# UniversalGlucometerV3.net
KiCad netlist of a schematic drawn in EAGLE
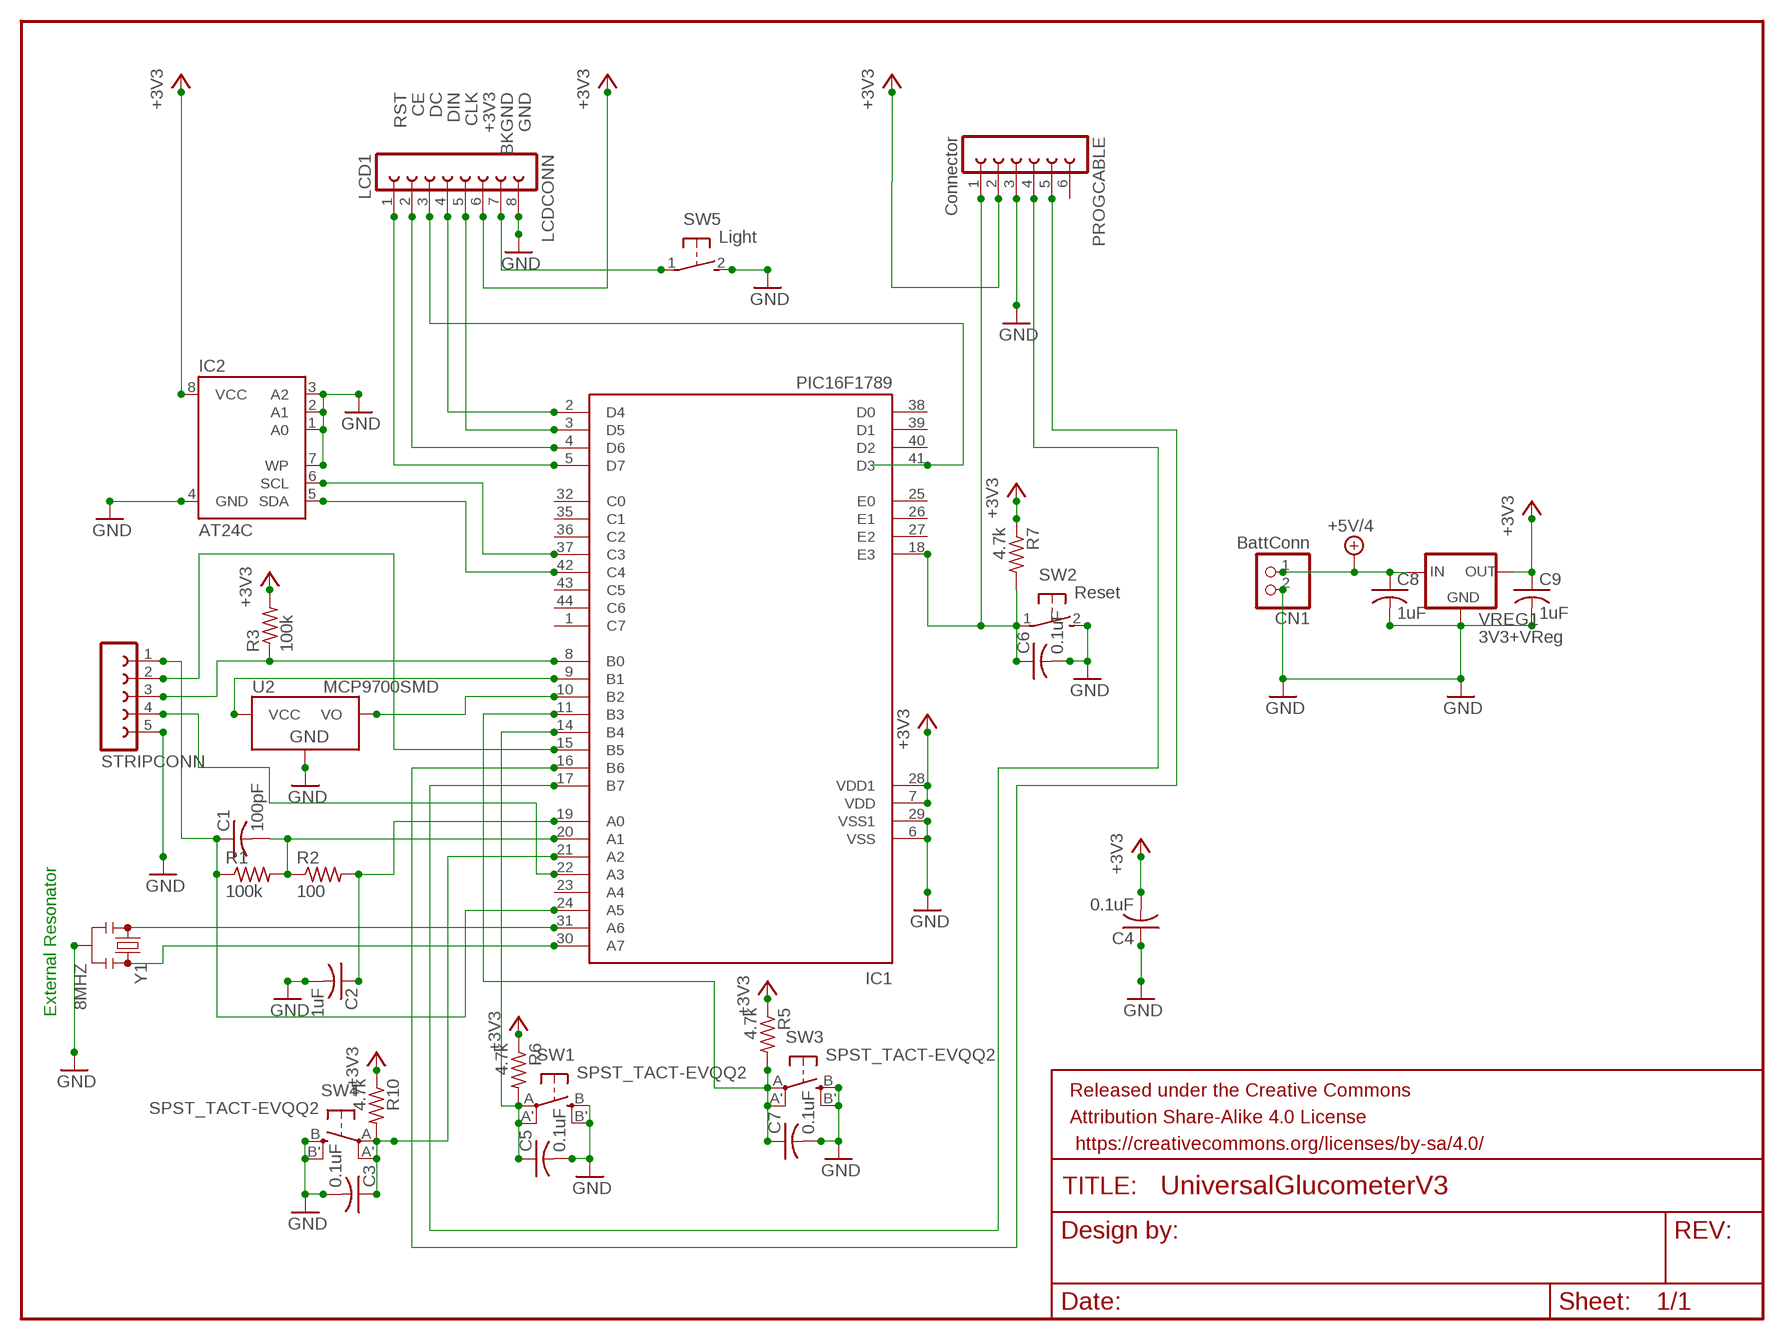
[diagram p0: schematic, sheet 1]

(export (version "E")
  (design (tool "Eeschema 10.0.6"))
  (components
    (comp (ref "C1")
      (value "100pF")
      (footprint "eagle-import:C0805")
      (libsource (lib "eagle-import") (part "C-USC0805"))
    )
    (comp (ref "C2")
      (value "1uF")
      (footprint "eagle-import:C0805")
      (libsource (lib "eagle-import") (part "C-USC0805"))
    )
    (comp (ref "C3")
      (value "0.1uF")
      (footprint "eagle-import:C0805")
      (libsource (lib "eagle-import") (part "C-USC0805"))
    )
    (comp (ref "C4")
      (value "0.1uF")
      (footprint "eagle-import:C0805")
      (libsource (lib "eagle-import") (part "C-USC0805"))
    )
    (comp (ref "C5")
      (value "0.1uF")
      (footprint "eagle-import:C0805")
      (libsource (lib "eagle-import") (part "C-USC0805"))
    )
    (comp (ref "C6")
      (value "0.1uF")
      (footprint "eagle-import:C0805")
      (libsource (lib "eagle-import") (part "C-USC0805"))
    )
    (comp (ref "C7")
      (value "0.1uF")
      (footprint "eagle-import:C0805")
      (libsource (lib "eagle-import") (part "C-USC0805"))
    )
    (comp (ref "C8")
      (value "1uF")
      (footprint "eagle-import:C0805")
      (libsource (lib "eagle-import") (part "C-USC0805"))
    )
    (comp (ref "C9")
      (value "1uF")
      (footprint "eagle-import:C0805")
      (libsource (lib "eagle-import") (part "C-USC0805"))
    )
    (comp (ref "CN1")
      (value "BattConn")
      (footprint "eagle-import:JST-PH-2-THM-RA")
      (libsource (lib "eagle-import") (part "JST_2PIN-THM-RA"))
    )
    (comp (ref "FRAME1")
      (value "FRAME-LETTER")
      (footprint "eagle-import:CREATIVE_COMMONS")
      (libsource (lib "eagle-import") (part "FRAME-LETTER"))
    )
    (comp (ref "IC1")
      (value "PIC16F1789")
      (footprint "eagle-import:TQFP44")
      (libsource (lib "eagle-import") (part "PIC16F1789"))
    )
    (comp (ref "IC2")
      (value "AT24C")
      (footprint "eagle-import:SOIC8")
      (libsource (lib "eagle-import") (part "AT24C"))
    )
    (comp (ref "LCDCONN")
      (value "LCD1")
      (footprint "eagle-import:FE08")
      (libsource (lib "eagle-import") (part "FE08-1"))
    )
    (comp (ref "PROGCABLE")
      (value "Connector")
      (footprint "eagle-import:FE06")
      (libsource (lib "eagle-import") (part "FE06-1"))
    )
    (comp (ref "R1")
      (value "100k")
      (footprint "eagle-import:R0805")
      (libsource (lib "eagle-import") (part "R-US_R0805"))
    )
    (comp (ref "R2")
      (value "100")
      (footprint "eagle-import:R0805")
      (libsource (lib "eagle-import") (part "R-US_R0805"))
    )
    (comp (ref "R3")
      (value "100k")
      (footprint "eagle-import:R0805")
      (libsource (lib "eagle-import") (part "R-US_R0805"))
    )
    (comp (ref "R5")
      (value "4.7k")
      (footprint "eagle-import:R0805")
      (libsource (lib "eagle-import") (part "R-US_R0805"))
    )
    (comp (ref "R6")
      (value "4.7k")
      (footprint "eagle-import:R0805")
      (libsource (lib "eagle-import") (part "R-US_R0805"))
    )
    (comp (ref "R7")
      (value "4.7k")
      (footprint "eagle-import:R0805")
      (libsource (lib "eagle-import") (part "R-US_R0805"))
    )
    (comp (ref "R10")
      (value "4.7k")
      (footprint "eagle-import:R0805")
      (libsource (lib "eagle-import") (part "R-US_R0805"))
    )
    (comp (ref "STRIPCONN")
      (value "FE05-1")
      (footprint "eagle-import:FE05-1")
      (libsource (lib "eagle-import") (part "FE05-1"))
    )
    (comp (ref "SW1")
      (value "SPST_TACT-EVQQ2")
      (footprint "eagle-import:EVQ-Q2")
      (libsource (lib "eagle-import") (part "SPST_TACT-EVQQ2"))
    )
    (comp (ref "SW2")
      (value "Reset")
      (footprint "eagle-import:B3F-31XX")
      (libsource (lib "eagle-import") (part "31-XX"))
    )
    (comp (ref "SW3")
      (value "SPST_TACT-EVQQ2")
      (footprint "eagle-import:EVQ-Q2")
      (libsource (lib "eagle-import") (part "SPST_TACT-EVQQ2"))
    )
    (comp (ref "SW4")
      (value "SPST_TACT-EVQQ2")
      (footprint "eagle-import:EVQ-Q2")
      (libsource (lib "eagle-import") (part "SPST_TACT-EVQQ2"))
    )
    (comp (ref "SW5")
      (value "Light")
      (footprint "eagle-import:B3F-31XX")
      (libsource (lib "eagle-import") (part "31-XX"))
    )
    (comp (ref "U2")
      (value "MCP9700SMD")
      (footprint "eagle-import:SOT23-3")
      (libsource (lib "eagle-import") (part "MCP9700SMD"))
    )
    (comp (ref "VREG1")
      (value "3V3+VReg")
      (footprint "eagle-import:SOT23-3")
      (libsource (lib "eagle-import") (part "MCP1700SOT23-3"))
    )
    (comp (ref "Y1")
      (value "8MHZ")
      (footprint "eagle-import:RESONATOR-SMD")
      (libsource (lib "eagle-import") (part "RESONATOR8MHZ"))
    )
  )
  (nets
    (net (code "1") (name "+3V3") (class "Default")
      (node (ref "C4") (pin "2") (pinfunction "2_2") (pintype "passive"))
      (node (ref "C9") (pin "1") (pinfunction "1_1") (pintype "passive"))
      (node (ref "IC1") (pin "28") (pinfunction "VDD1_28") (pintype "power_in"))
      (node (ref "IC1") (pin "7") (pinfunction "VDD_7") (pintype "power_in"))
      (node (ref "IC2") (pin "8") (pinfunction "VCC_8") (pintype "power_in"))
      (node (ref "LCDCONN") (pin "6") (pinfunction "6_6") (pintype "passive"))
      (node (ref "PROGCABLE") (pin "2") (pinfunction "2_2") (pintype "passive"))
      (node (ref "R10") (pin "1") (pinfunction "1_1") (pintype "passive"))
      (node (ref "R3") (pin "2") (pinfunction "2_2") (pintype "passive"))
      (node (ref "R5") (pin "1") (pinfunction "1_1") (pintype "passive"))
      (node (ref "R6") (pin "1") (pinfunction "1_1") (pintype "passive"))
      (node (ref "R7") (pin "1") (pinfunction "1_1") (pintype "passive"))
      (node (ref "VREG1") (pin "2") (pinfunction "OUT_2") (pintype "passive"))
    )
    (net (code "2") (name "+5V{slash}4") (class "Default")
      (node (ref "C8") (pin "1") (pinfunction "1_1") (pintype "passive"))
      (node (ref "CN1") (pin "1") (pinfunction "2_1") (pintype "passive"))
      (node (ref "VREG1") (pin "3") (pinfunction "IN_3") (pintype "input"))
    )
    (net (code "3") (name "/BKGND") (class "Default")
      (node (ref "LCDCONN") (pin "7") (pinfunction "7_7") (pintype "passive"))
      (node (ref "SW5") (pin "1") (pinfunction "P_1") (pintype "passive"))
    )
    (net (code "4") (name "/CE") (class "Default")
      (node (ref "IC1") (pin "4") (pinfunction "D6_4") (pintype "bidirectional"))
      (node (ref "LCDCONN") (pin "2") (pinfunction "2_2") (pintype "passive"))
    )
    (net (code "5") (name "/CLK") (class "Default")
      (node (ref "IC1") (pin "3") (pinfunction "D5_3") (pintype "bidirectional"))
      (node (ref "LCDCONN") (pin "5") (pinfunction "5_5") (pintype "passive"))
    )
    (net (code "6") (name "/DC") (class "Default")
      (node (ref "IC1") (pin "41") (pinfunction "D3_41") (pintype "bidirectional"))
      (node (ref "LCDCONN") (pin "3") (pinfunction "3_3") (pintype "passive"))
    )
    (net (code "7") (name "/DIN") (class "Default")
      (node (ref "IC1") (pin "2") (pinfunction "D4_2") (pintype "bidirectional"))
      (node (ref "LCDCONN") (pin "4") (pinfunction "4_4") (pintype "passive"))
    )
    (net (code "8") (name "/RST") (class "Default")
      (node (ref "IC1") (pin "5") (pinfunction "D7_5") (pintype "bidirectional"))
      (node (ref "LCDCONN") (pin "1") (pinfunction "1_1") (pintype "passive"))
    )
    (net (code "9") (name "GND") (class "Default")
      (node (ref "C2") (pin "2") (pinfunction "2_2") (pintype "passive"))
      (node (ref "C3") (pin "2") (pinfunction "2_2") (pintype "passive"))
      (node (ref "C4") (pin "1") (pinfunction "1_1") (pintype "passive"))
      (node (ref "C5") (pin "2") (pinfunction "2_2") (pintype "passive"))
      (node (ref "C6") (pin "2") (pinfunction "2_2") (pintype "passive"))
      (node (ref "C7") (pin "2") (pinfunction "2_2") (pintype "passive"))
      (node (ref "C8") (pin "2") (pinfunction "2_2") (pintype "passive"))
      (node (ref "C9") (pin "2") (pinfunction "2_2") (pintype "passive"))
      (node (ref "CN1") (pin "2") (pinfunction "1_2") (pintype "passive"))
      (node (ref "IC1") (pin "29") (pinfunction "VSS1_29") (pintype "power_in"))
      (node (ref "IC1") (pin "6") (pinfunction "VSS_6") (pintype "power_in"))
      (node (ref "IC2") (pin "1") (pinfunction "A0_1") (pintype "input"))
      (node (ref "IC2") (pin "2") (pinfunction "A1_2") (pintype "input"))
      (node (ref "IC2") (pin "3") (pinfunction "A2_3") (pintype "input"))
      (node (ref "IC2") (pin "4") (pinfunction "GND_4") (pintype "power_in"))
      (node (ref "IC2") (pin "7") (pinfunction "WP_7") (pintype "input"))
      (node (ref "LCDCONN") (pin "8") (pinfunction "8_8") (pintype "passive"))
      (node (ref "PROGCABLE") (pin "3") (pinfunction "3_3") (pintype "passive"))
      (node (ref "STRIPCONN") (pin "5") (pinfunction "5_5") (pintype "passive"))
      (node (ref "SW1") (pin "B") (pinfunction "S_B") (pintype "passive"))
      (node (ref "SW1") (pin "B'") (pinfunction "S1_B'") (pintype "passive"))
      (node (ref "SW2") (pin "2") (pinfunction "S_2") (pintype "passive"))
      (node (ref "SW3") (pin "B") (pinfunction "S_B") (pintype "passive"))
      (node (ref "SW3") (pin "B'") (pinfunction "S1_B'") (pintype "passive"))
      (node (ref "SW4") (pin "B") (pinfunction "S_B") (pintype "passive"))
      (node (ref "SW4") (pin "B'") (pinfunction "S1_B'") (pintype "passive"))
      (node (ref "SW5") (pin "2") (pinfunction "S_2") (pintype "passive"))
      (node (ref "U2") (pin "3") (pinfunction "GND_3") (pintype "bidirectional"))
      (node (ref "VREG1") (pin "1") (pinfunction "GND_1") (pintype "input"))
      (node (ref "Y1") (pin "2") (pinfunction "2_2") (pintype "passive"))
    )
    (net (code "10") (name "Net-(IC1-A0)") (class "Default")
      (node (ref "C2") (pin "1") (pinfunction "1_1") (pintype "passive"))
      (node (ref "IC1") (pin "19") (pinfunction "A0_19") (pintype "bidirectional"))
      (node (ref "R2") (pin "2") (pinfunction "2_2") (pintype "passive"))
    )
    (net (code "11") (name "Net-(IC1-A1)") (class "Default")
      (node (ref "C1") (pin "2") (pinfunction "2_2") (pintype "passive"))
      (node (ref "IC1") (pin "20") (pinfunction "A1_20") (pintype "bidirectional"))
      (node (ref "R1") (pin "2") (pinfunction "2_2") (pintype "passive"))
      (node (ref "R2") (pin "1") (pinfunction "1_1") (pintype "passive"))
    )
    (net (code "12") (name "Net-(IC1-A2)") (class "Default")
      (node (ref "C3") (pin "1") (pinfunction "1_1") (pintype "passive"))
      (node (ref "IC1") (pin "21") (pinfunction "A2_21") (pintype "bidirectional"))
      (node (ref "R10") (pin "2") (pinfunction "2_2") (pintype "passive"))
      (node (ref "SW4") (pin "A") (pinfunction "P_A") (pintype "passive"))
      (node (ref "SW4") (pin "A'") (pinfunction "P1_A'") (pintype "passive"))
    )
    (net (code "13") (name "Net-(IC1-A3)") (class "Default")
      (node (ref "IC1") (pin "22") (pinfunction "A3_22") (pintype "bidirectional"))
      (node (ref "STRIPCONN") (pin "4") (pinfunction "4_4") (pintype "passive"))
    )
    (net (code "14") (name "Net-(IC1-A5)") (class "Default")
      (node (ref "C1") (pin "1") (pinfunction "1_1") (pintype "passive"))
      (node (ref "IC1") (pin "24") (pinfunction "A5_24") (pintype "bidirectional"))
      (node (ref "R1") (pin "1") (pinfunction "1_1") (pintype "passive"))
      (node (ref "STRIPCONN") (pin "1") (pinfunction "1_1") (pintype "passive"))
    )
    (net (code "15") (name "Net-(IC1-A6)") (class "Default")
      (node (ref "IC1") (pin "31") (pinfunction "A6_31") (pintype "bidirectional"))
      (node (ref "Y1") (pin "1") (pinfunction "1_1") (pintype "passive"))
    )
    (net (code "16") (name "Net-(IC1-A7)") (class "Default")
      (node (ref "IC1") (pin "30") (pinfunction "A7_30") (pintype "bidirectional"))
      (node (ref "Y1") (pin "3") (pinfunction "3_3") (pintype "passive"))
    )
    (net (code "17") (name "Net-(IC1-B0)") (class "Default")
      (node (ref "IC1") (pin "8") (pinfunction "B0_8") (pintype "bidirectional"))
      (node (ref "R3") (pin "1") (pinfunction "1_1") (pintype "passive"))
      (node (ref "STRIPCONN") (pin "3") (pinfunction "3_3") (pintype "passive"))
    )
    (net (code "18") (name "Net-(IC1-B1)") (class "Default")
      (node (ref "IC1") (pin "9") (pinfunction "B1_9") (pintype "bidirectional"))
      (node (ref "U2") (pin "1") (pinfunction "VCC_1") (pintype "bidirectional"))
    )
    (net (code "19") (name "Net-(IC1-B2)") (class "Default")
      (node (ref "IC1") (pin "10") (pinfunction "B2_10") (pintype "bidirectional"))
      (node (ref "U2") (pin "2") (pinfunction "VO_2") (pintype "bidirectional"))
    )
    (net (code "20") (name "Net-(IC1-B3)") (class "Default")
      (node (ref "C7") (pin "1") (pinfunction "1_1") (pintype "passive"))
      (node (ref "IC1") (pin "11") (pinfunction "B3_11") (pintype "bidirectional"))
      (node (ref "R5") (pin "2") (pinfunction "2_2") (pintype "passive"))
      (node (ref "SW3") (pin "A") (pinfunction "P_A") (pintype "passive"))
      (node (ref "SW3") (pin "A'") (pinfunction "P1_A'") (pintype "passive"))
    )
    (net (code "21") (name "Net-(IC1-B4)") (class "Default")
      (node (ref "C5") (pin "1") (pinfunction "1_1") (pintype "passive"))
      (node (ref "IC1") (pin "14") (pinfunction "B4_14") (pintype "bidirectional"))
      (node (ref "R6") (pin "2") (pinfunction "2_2") (pintype "passive"))
      (node (ref "SW1") (pin "A") (pinfunction "P_A") (pintype "passive"))
      (node (ref "SW1") (pin "A'") (pinfunction "P1_A'") (pintype "passive"))
    )
    (net (code "22") (name "Net-(IC1-B5)") (class "Default")
      (node (ref "IC1") (pin "15") (pinfunction "B5_15") (pintype "bidirectional"))
      (node (ref "STRIPCONN") (pin "2") (pinfunction "2_2") (pintype "passive"))
    )
    (net (code "23") (name "Net-(IC1-B6)") (class "Default")
      (node (ref "IC1") (pin "16") (pinfunction "B6_16") (pintype "bidirectional"))
      (node (ref "PROGCABLE") (pin "5") (pinfunction "5_5") (pintype "passive"))
    )
    (net (code "24") (name "Net-(IC1-B7)") (class "Default")
      (node (ref "IC1") (pin "17") (pinfunction "B7_17") (pintype "bidirectional"))
      (node (ref "PROGCABLE") (pin "4") (pinfunction "4_4") (pintype "passive"))
    )
    (net (code "25") (name "Net-(IC1-C3)") (class "Default")
      (node (ref "IC1") (pin "37") (pinfunction "C3_37") (pintype "bidirectional"))
      (node (ref "IC2") (pin "6") (pinfunction "SCL_6") (pintype "bidirectional"))
    )
    (net (code "26") (name "Net-(IC1-C4)") (class "Default")
      (node (ref "IC1") (pin "42") (pinfunction "C4_42") (pintype "bidirectional"))
      (node (ref "IC2") (pin "5") (pinfunction "SDA_5") (pintype "bidirectional"))
    )
    (net (code "27") (name "Net-(IC1-E3)") (class "Default")
      (node (ref "C6") (pin "1") (pinfunction "1_1") (pintype "passive"))
      (node (ref "IC1") (pin "18") (pinfunction "E3_18") (pintype "bidirectional"))
      (node (ref "PROGCABLE") (pin "1") (pinfunction "1_1") (pintype "passive"))
      (node (ref "R7") (pin "2") (pinfunction "2_2") (pintype "passive"))
      (node (ref "SW2") (pin "1") (pinfunction "P_1") (pintype "passive"))
    )
    (net (code "28") (name "unconnected-(IC1-A4-Pad23)") (class "Default")
      (node (ref "IC1") (pin "23") (pinfunction "A4_23") (pintype "bidirectional"))
    )
    (net (code "29") (name "unconnected-(IC1-C0-Pad32)") (class "Default")
      (node (ref "IC1") (pin "32") (pinfunction "C0_32") (pintype "bidirectional"))
    )
    (net (code "30") (name "unconnected-(IC1-C1-Pad35)") (class "Default")
      (node (ref "IC1") (pin "35") (pinfunction "C1_35") (pintype "bidirectional"))
    )
    (net (code "31") (name "unconnected-(IC1-C2-Pad36)") (class "Default")
      (node (ref "IC1") (pin "36") (pinfunction "C2_36") (pintype "bidirectional"))
    )
    (net (code "32") (name "unconnected-(IC1-C5-Pad43)") (class "Default")
      (node (ref "IC1") (pin "43") (pinfunction "C5_43") (pintype "bidirectional"))
    )
    (net (code "33") (name "unconnected-(IC1-C6-Pad44)") (class "Default")
      (node (ref "IC1") (pin "44") (pinfunction "C6_44") (pintype "bidirectional"))
    )
    (net (code "34") (name "unconnected-(IC1-C7-Pad1)") (class "Default")
      (node (ref "IC1") (pin "1") (pinfunction "C7_1") (pintype "bidirectional"))
    )
    (net (code "35") (name "unconnected-(IC1-D0-Pad38)") (class "Default")
      (node (ref "IC1") (pin "38") (pinfunction "D0_38") (pintype "bidirectional"))
    )
    (net (code "36") (name "unconnected-(IC1-D1-Pad39)") (class "Default")
      (node (ref "IC1") (pin "39") (pinfunction "D1_39") (pintype "bidirectional"))
    )
    (net (code "37") (name "unconnected-(IC1-D2-Pad40)") (class "Default")
      (node (ref "IC1") (pin "40") (pinfunction "D2_40") (pintype "bidirectional"))
    )
    (net (code "38") (name "unconnected-(IC1-E0-Pad25)") (class "Default")
      (node (ref "IC1") (pin "25") (pinfunction "E0_25") (pintype "bidirectional"))
    )
    (net (code "39") (name "unconnected-(IC1-E1-Pad26)") (class "Default")
      (node (ref "IC1") (pin "26") (pinfunction "E1_26") (pintype "bidirectional"))
    )
    (net (code "40") (name "unconnected-(IC1-E2-Pad27)") (class "Default")
      (node (ref "IC1") (pin "27") (pinfunction "E2_27") (pintype "bidirectional"))
    )
    (net (code "41") (name "unconnected-(PROGCABLE-Pad6)") (class "Default")
      (node (ref "PROGCABLE") (pin "6") (pinfunction "6_6") (pintype "passive"))
    )
  )
)
